# micromouse.net
KiCad netlist of a schematic drawn in EAGLE
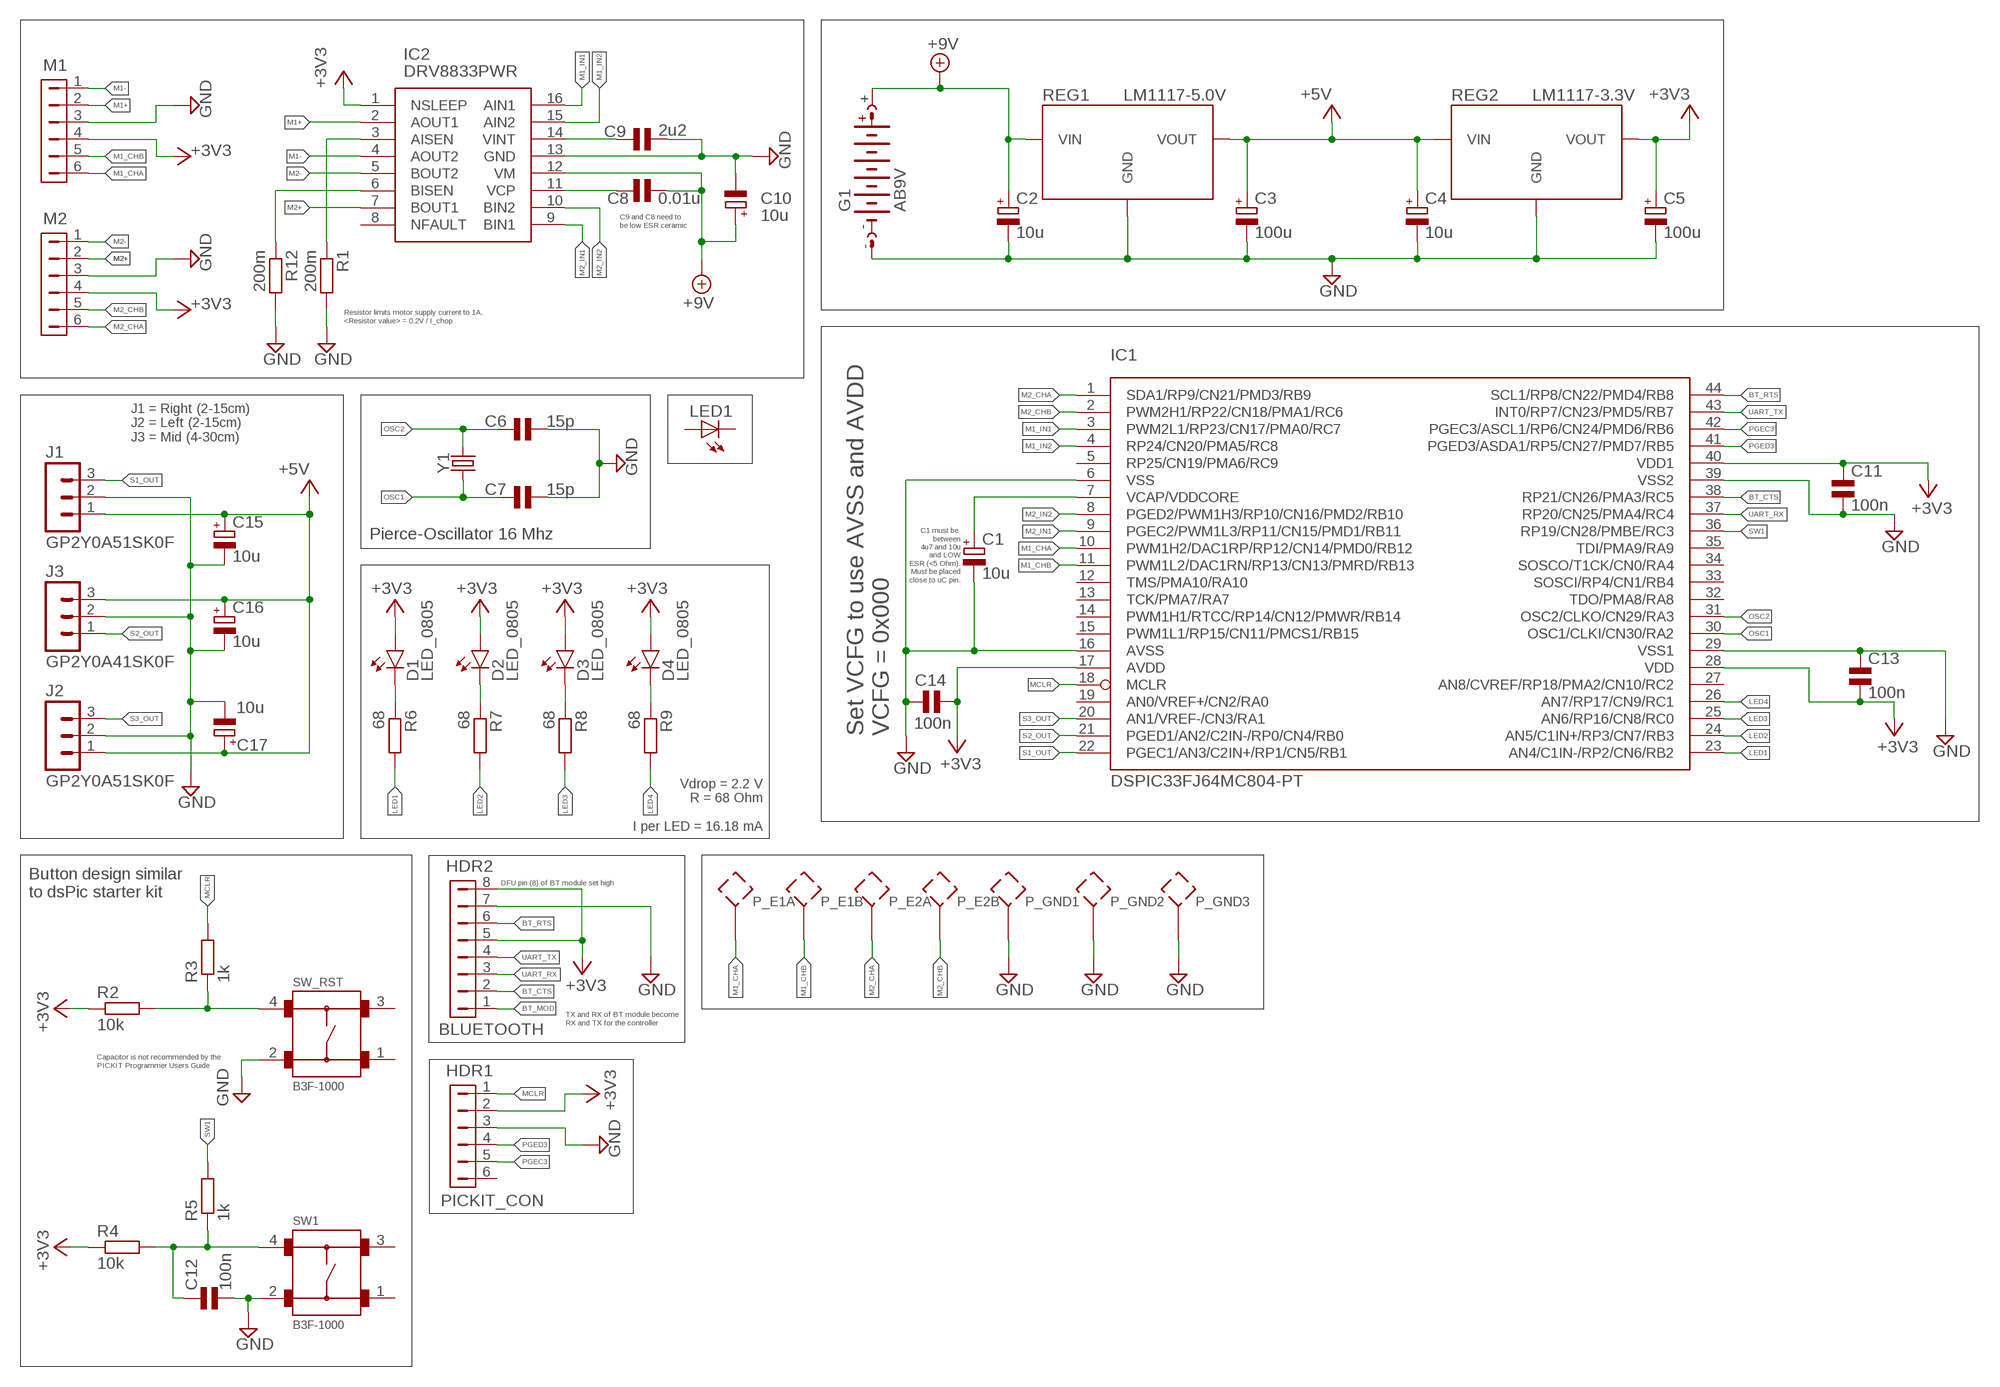
[diagram p0: schematic, sheet 1]

(export (version "E")
  (design (tool "Eeschema 10.0.6"))
  (components
    (comp (ref "C1")
      (value "10u")
      (footprint "eagle-import:0805_POL")
      (libsource (lib "eagle-import") (part "CPOL_0805"))
    )
    (comp (ref "C2")
      (value "10u")
      (footprint "eagle-import:0805_POL")
      (libsource (lib "eagle-import") (part "CPOL_0805"))
    )
    (comp (ref "C3")
      (value "100u")
      (footprint "eagle-import:0805_POL")
      (libsource (lib "eagle-import") (part "CPOL_0805"))
    )
    (comp (ref "C4")
      (value "10u")
      (footprint "eagle-import:0805_POL")
      (libsource (lib "eagle-import") (part "CPOL_0805"))
    )
    (comp (ref "C5")
      (value "100u")
      (footprint "eagle-import:0805_POL")
      (libsource (lib "eagle-import") (part "CPOL_0805"))
    )
    (comp (ref "C6")
      (value "15p")
      (footprint "eagle-import:0805")
      (libsource (lib "eagle-import") (part "C_0805"))
    )
    (comp (ref "C7")
      (value "15p")
      (footprint "eagle-import:0805")
      (libsource (lib "eagle-import") (part "C_0805"))
    )
    (comp (ref "C8")
      (value "0.01u")
      (footprint "eagle-import:0805")
      (libsource (lib "eagle-import") (part "C_0805"))
    )
    (comp (ref "C9")
      (value "2u2")
      (footprint "eagle-import:0805")
      (libsource (lib "eagle-import") (part "C_0805"))
    )
    (comp (ref "C10")
      (value "10u")
      (footprint "eagle-import:0805_POL")
      (libsource (lib "eagle-import") (part "CPOL_0805"))
    )
    (comp (ref "C11")
      (value "100n")
      (footprint "eagle-import:0805")
      (libsource (lib "eagle-import") (part "C_0805"))
    )
    (comp (ref "C12")
      (value "100n")
      (footprint "eagle-import:0805")
      (libsource (lib "eagle-import") (part "C_0805"))
    )
    (comp (ref "C13")
      (value "100n")
      (footprint "eagle-import:0805")
      (libsource (lib "eagle-import") (part "C_0805"))
    )
    (comp (ref "C14")
      (value "100n")
      (footprint "eagle-import:0805")
      (libsource (lib "eagle-import") (part "C_0805"))
    )
    (comp (ref "C15")
      (value "10u")
      (footprint "eagle-import:0805_POL")
      (libsource (lib "eagle-import") (part "CPOL_0805"))
    )
    (comp (ref "C16")
      (value "10u")
      (footprint "eagle-import:0805_POL")
      (libsource (lib "eagle-import") (part "CPOL_0805"))
    )
    (comp (ref "C17")
      (value "10u")
      (footprint "eagle-import:0805_POL")
      (libsource (lib "eagle-import") (part "CPOL_0805"))
    )
    (comp (ref "D1")
      (value "LED_0805")
      (footprint "eagle-import:SMD_LED_0805")
      (libsource (lib "eagle-import") (part "LED_0805"))
    )
    (comp (ref "D2")
      (value "LED_0805")
      (footprint "eagle-import:SMD_LED_0805")
      (libsource (lib "eagle-import") (part "LED_0805"))
    )
    (comp (ref "D3")
      (value "LED_0805")
      (footprint "eagle-import:SMD_LED_0805")
      (libsource (lib "eagle-import") (part "LED_0805"))
    )
    (comp (ref "D4")
      (value "LED_0805")
      (footprint "eagle-import:SMD_LED_0805")
      (libsource (lib "eagle-import") (part "LED_0805"))
    )
    (comp (ref "G1")
      (value "AB9V")
      (footprint "eagle-import:AB9V")
      (libsource (lib "eagle-import") (part "AB9V"))
    )
    (comp (ref "HDR1")
      (value "PICKIT_CON")
      (footprint "eagle-import:6PIN")
      (libsource (lib "eagle-import") (part "PICKIT_CON"))
    )
    (comp (ref "HDR2")
      (value "BLUETOOTH")
      (footprint "eagle-import:1X08")
      (libsource (lib "eagle-import") (part "BLUETOOTHSHIELD"))
    )
    (comp (ref "IC1")
      (value "DSPIC33FJ64MC804-PT")
      (footprint "eagle-import:TQFP44")
      (libsource (lib "eagle-import") (part "DSPIC33FJ64MC804-PT"))
    )
    (comp (ref "IC2")
      (value "DRV8833PWR")
      (footprint "eagle-import:SOP65P640X120-16N")
      (fields (field (name "MOUSER_PART_NUMBER") "595-DRV8833PWR"))
      (libsource (lib "eagle-import") (part "DRV8833PWR"))
    )
    (comp (ref "J1")
      (value "GP2Y0A51SK0F")
      (footprint "eagle-import:B3B-ZR(LF)(SN)")
      (libsource (lib "eagle-import") (part "B3B-ZR"))
    )
    (comp (ref "J2")
      (value "GP2Y0A51SK0F")
      (footprint "eagle-import:B3B-ZR(LF)(SN)")
      (libsource (lib "eagle-import") (part "B3B-ZR"))
    )
    (comp (ref "J3")
      (value "GP2Y0A41SK0F")
      (footprint "eagle-import:B3B-PH-K-S")
      (libsource (lib "eagle-import") (part "B3B-PH-K-S"))
    )
    (comp (ref "LED1")
      (value "LED5MM")
      (footprint "eagle-import:LED5MM")
      (libsource (lib "eagle-import") (part "LED5MM"))
    )
    (comp (ref "M1")
      (value "MOTOR_CON")
      (footprint "eagle-import:JP3Q")
      (libsource (lib "eagle-import") (part "MOTOR_CON"))
    )
    (comp (ref "M2")
      (value "MOTOR_CON")
      (footprint "eagle-import:JP3Q")
      (libsource (lib "eagle-import") (part "MOTOR_CON"))
    )
    (comp (ref "P_E1A")
      (value "PROBE_POINTTHT")
      (footprint "eagle-import:PROBEPOINT_THT")
      (libsource (lib "eagle-import") (part "PROBE_POINTTHT"))
    )
    (comp (ref "P_E1B")
      (value "PROBE_POINTTHT")
      (footprint "eagle-import:PROBEPOINT_THT")
      (libsource (lib "eagle-import") (part "PROBE_POINTTHT"))
    )
    (comp (ref "P_E2A")
      (value "PROBE_POINTTHT")
      (footprint "eagle-import:PROBEPOINT_THT")
      (libsource (lib "eagle-import") (part "PROBE_POINTTHT"))
    )
    (comp (ref "P_E2B")
      (value "PROBE_POINTTHT")
      (footprint "eagle-import:PROBEPOINT_THT")
      (libsource (lib "eagle-import") (part "PROBE_POINTTHT"))
    )
    (comp (ref "P_GND1")
      (value "PROBE_POINTTHT")
      (footprint "eagle-import:PROBEPOINT_THT")
      (libsource (lib "eagle-import") (part "PROBE_POINTTHT"))
    )
    (comp (ref "P_GND2")
      (value "PROBE_POINTTHT")
      (footprint "eagle-import:PROBEPOINT_THT")
      (libsource (lib "eagle-import") (part "PROBE_POINTTHT"))
    )
    (comp (ref "P_GND3")
      (value "PROBE_POINTTHT")
      (footprint "eagle-import:PROBEPOINT_THT")
      (libsource (lib "eagle-import") (part "PROBE_POINTTHT"))
    )
    (comp (ref "R1")
      (value "200m")
      (footprint "eagle-import:0805")
      (libsource (lib "eagle-import") (part "R_0805"))
    )
    (comp (ref "R2")
      (value "10k")
      (footprint "eagle-import:0805")
      (libsource (lib "eagle-import") (part "R_0805"))
    )
    (comp (ref "R3")
      (value "1k")
      (footprint "eagle-import:0805")
      (libsource (lib "eagle-import") (part "R_0805"))
    )
    (comp (ref "R4")
      (value "10k")
      (footprint "eagle-import:0805")
      (libsource (lib "eagle-import") (part "R_0805"))
    )
    (comp (ref "R5")
      (value "1k")
      (footprint "eagle-import:0805")
      (libsource (lib "eagle-import") (part "R_0805"))
    )
    (comp (ref "R6")
      (value "68")
      (footprint "eagle-import:0805")
      (libsource (lib "eagle-import") (part "R_0805"))
    )
    (comp (ref "R7")
      (value "68")
      (footprint "eagle-import:0805")
      (libsource (lib "eagle-import") (part "R_0805"))
    )
    (comp (ref "R8")
      (value "68")
      (footprint "eagle-import:0805")
      (libsource (lib "eagle-import") (part "R_0805"))
    )
    (comp (ref "R9")
      (value "68")
      (footprint "eagle-import:0805")
      (libsource (lib "eagle-import") (part "R_0805"))
    )
    (comp (ref "R12")
      (value "200m")
      (footprint "eagle-import:0805")
      (libsource (lib "eagle-import") (part "R_0805"))
    )
    (comp (ref "REG1")
      (value "LM1117-5.0V")
      (footprint "eagle-import:SOT-223-4")
      (libsource (lib "eagle-import") (part "LM1117_SOT223"))
    )
    (comp (ref "REG2")
      (value "LM1117-3.3V")
      (footprint "eagle-import:SOT-223-4")
      (libsource (lib "eagle-import") (part "LM1117_SOT223"))
    )
    (comp (ref "SW1")
      (value "B3F-1000")
      (footprint "eagle-import:B3F-1000")
      (fields
        (field (name "DIGI_KEY_PART_NUMBER") "SW400-ND")
        (field (name "MANUFACTURER") "Omron Electronics Inc-EMC Div")
        (field (name "CREATED_BY") "PCBLayout.com")
      )
      (libsource (lib "eagle-import") (part "B3F-1000"))
    )
    (comp (ref "SW_RST")
      (value "B3F-1000")
      (footprint "eagle-import:B3F-1000")
      (fields
        (field (name "DIGI_KEY_PART_NUMBER") "SW400-ND")
        (field (name "MANUFACTURER") "Omron Electronics Inc-EMC Div")
        (field (name "CREATED_BY") "PCBLayout.com")
      )
      (libsource (lib "eagle-import") (part "B3F-1000"))
    )
    (comp (ref "Y1")
      (value "CRYSTALPTH-HC49US")
      (footprint "eagle-import:HC49US")
      (libsource (lib "eagle-import") (part "CRYSTALPTH-HC49US"))
    )
  )
  (nets
    (net (code "1") (name "+3V3") (class "Default")
      (node (ref "C11") (pin "1") (pinfunction "+_1") (pintype "passive"))
      (node (ref "C13") (pin "2") (pinfunction "-_2") (pintype "passive"))
      (node (ref "C14") (pin "2") (pinfunction "-_2") (pintype "passive"))
      (node (ref "C5") (pin "1") (pinfunction "+_1") (pintype "passive"))
      (node (ref "D1") (pin "P$2") (pinfunction "A_P$2") (pintype "passive"))
      (node (ref "D2") (pin "P$2") (pinfunction "A_P$2") (pintype "passive"))
      (node (ref "D3") (pin "P$2") (pinfunction "A_P$2") (pintype "passive"))
      (node (ref "D4") (pin "P$2") (pinfunction "A_P$2") (pintype "passive"))
      (node (ref "HDR1") (pin "2") (pinfunction "2_2") (pintype "passive"))
      (node (ref "HDR2") (pin "5") (pinfunction "5_5") (pintype "passive"))
      (node (ref "HDR2") (pin "8") (pinfunction "8_8") (pintype "passive"))
      (node (ref "IC1") (pin "17") (pinfunction "AVDD_17") (pintype "power_in"))
      (node (ref "IC1") (pin "28") (pinfunction "VDD_28") (pintype "power_in"))
      (node (ref "IC1") (pin "40") (pinfunction "VDD1_40") (pintype "power_in"))
      (node (ref "IC2") (pin "1") (pinfunction "NSLEEP_1") (pintype "bidirectional"))
      (node (ref "M1") (pin "4") (pinfunction "4_4") (pintype "passive"))
      (node (ref "M2") (pin "4") (pinfunction "4_4") (pintype "passive"))
      (node (ref "R2") (pin "1") (pinfunction "1_1") (pintype "passive"))
      (node (ref "R4") (pin "1") (pinfunction "1_1") (pintype "passive"))
      (node (ref "REG2") (pin "2") (pinfunction "VOUT_2") (pintype "bidirectional"))
      (node (ref "REG2") (pin "4") (pinfunction "VOUT_4") (pintype "bidirectional"))
    )
    (net (code "2") (name "+5V") (class "Default")
      (node (ref "C15") (pin "1") (pinfunction "+_1") (pintype "passive"))
      (node (ref "C16") (pin "1") (pinfunction "+_1") (pintype "passive"))
      (node (ref "C17") (pin "1") (pinfunction "+_1") (pintype "passive"))
      (node (ref "C3") (pin "1") (pinfunction "+_1") (pintype "passive"))
      (node (ref "C4") (pin "1") (pinfunction "+_1") (pintype "passive"))
      (node (ref "J1") (pin "1") (pinfunction "1_1") (pintype "passive"))
      (node (ref "J2") (pin "1") (pinfunction "1_1") (pintype "passive"))
      (node (ref "J3") (pin "3") (pinfunction "3_3") (pintype "passive"))
      (node (ref "REG1") (pin "2") (pinfunction "VOUT_2") (pintype "bidirectional"))
      (node (ref "REG1") (pin "4") (pinfunction "VOUT_4") (pintype "bidirectional"))
      (node (ref "REG2") (pin "3") (pinfunction "VIN_3") (pintype "bidirectional"))
    )
    (net (code "3") (name "+9V") (class "Default")
      (node (ref "C10") (pin "1") (pinfunction "+_1") (pintype "passive"))
      (node (ref "C2") (pin "1") (pinfunction "+_1") (pintype "passive"))
      (node (ref "C8") (pin "1") (pinfunction "+_1") (pintype "passive"))
      (node (ref "G1") (pin "+") (pinfunction "+_+") (pintype "passive"))
      (node (ref "IC2") (pin "12") (pinfunction "VM_12") (pintype "bidirectional"))
      (node (ref "REG1") (pin "3") (pinfunction "VIN_3") (pintype "bidirectional"))
    )
    (net (code "4") (name "BT_CTS") (class "Default")
      (node (ref "HDR2") (pin "2") (pinfunction "2_2") (pintype "passive"))
      (node (ref "IC1") (pin "38") (pinfunction "RP21/CN26/PMA3/RC5_38") (pintype "bidirectional"))
    )
    (net (code "5") (name "BT_MOD") (class "Default")
      (node (ref "HDR2") (pin "1") (pinfunction "1_1") (pintype "passive"))
    )
    (net (code "6") (name "BT_RTS") (class "Default")
      (node (ref "HDR2") (pin "6") (pinfunction "6_6") (pintype "passive"))
      (node (ref "IC1") (pin "44") (pinfunction "SCL1/RP8/CN22/PMD4/RB8_44") (pintype "bidirectional"))
    )
    (net (code "7") (name "GND") (class "Default")
      (node (ref "C1") (pin "2") (pinfunction "-_2") (pintype "passive"))
      (node (ref "C10") (pin "2") (pinfunction "-_2") (pintype "passive"))
      (node (ref "C11") (pin "2") (pinfunction "-_2") (pintype "passive"))
      (node (ref "C12") (pin "2") (pinfunction "-_2") (pintype "passive"))
      (node (ref "C13") (pin "1") (pinfunction "+_1") (pintype "passive"))
      (node (ref "C14") (pin "1") (pinfunction "+_1") (pintype "passive"))
      (node (ref "C15") (pin "2") (pinfunction "-_2") (pintype "passive"))
      (node (ref "C16") (pin "2") (pinfunction "-_2") (pintype "passive"))
      (node (ref "C17") (pin "2") (pinfunction "-_2") (pintype "passive"))
      (node (ref "C2") (pin "2") (pinfunction "-_2") (pintype "passive"))
      (node (ref "C3") (pin "2") (pinfunction "-_2") (pintype "passive"))
      (node (ref "C4") (pin "2") (pinfunction "-_2") (pintype "passive"))
      (node (ref "C5") (pin "2") (pinfunction "-_2") (pintype "passive"))
      (node (ref "C6") (pin "2") (pinfunction "-_2") (pintype "passive"))
      (node (ref "C7") (pin "2") (pinfunction "-_2") (pintype "passive"))
      (node (ref "C9") (pin "2") (pinfunction "-_2") (pintype "passive"))
      (node (ref "G1") (pin "-") (pinfunction "-_-") (pintype "passive"))
      (node (ref "HDR1") (pin "3") (pinfunction "3_3") (pintype "passive"))
      (node (ref "HDR2") (pin "7") (pinfunction "7_7") (pintype "passive"))
      (node (ref "IC1") (pin "16") (pinfunction "AVSS_16") (pintype "power_in"))
      (node (ref "IC1") (pin "29") (pinfunction "VSS1_29") (pintype "power_in"))
      (node (ref "IC1") (pin "39") (pinfunction "VSS2_39") (pintype "power_in"))
      (node (ref "IC1") (pin "6") (pinfunction "VSS_6") (pintype "power_in"))
      (node (ref "IC2") (pin "13") (pinfunction "GND_13") (pintype "bidirectional"))
      (node (ref "J1") (pin "2") (pinfunction "2_2") (pintype "passive"))
      (node (ref "J2") (pin "2") (pinfunction "2_2") (pintype "passive"))
      (node (ref "J3") (pin "2") (pinfunction "2_2") (pintype "passive"))
      (node (ref "M1") (pin "3") (pinfunction "3_3") (pintype "passive"))
      (node (ref "M2") (pin "3") (pinfunction "3_3") (pintype "passive"))
      (node (ref "P_GND1") (pin "P$1") (pinfunction "P$1_P$1") (pintype "bidirectional"))
      (node (ref "P_GND2") (pin "P$1") (pinfunction "P$1_P$1") (pintype "bidirectional"))
      (node (ref "P_GND3") (pin "P$1") (pinfunction "P$1_P$1") (pintype "bidirectional"))
      (node (ref "R1") (pin "2") (pinfunction "2_2") (pintype "passive"))
      (node (ref "R12") (pin "2") (pinfunction "2_2") (pintype "passive"))
      (node (ref "REG1") (pin "1") (pinfunction "GND_1") (pintype "bidirectional"))
      (node (ref "REG2") (pin "1") (pinfunction "GND_1") (pintype "bidirectional"))
      (node (ref "SW1") (pin "2") (pinfunction "2_2") (pintype "passive"))
      (node (ref "SW_RST") (pin "2") (pinfunction "2_2") (pintype "passive"))
    )
    (net (code "8") (name "LED1") (class "Default")
      (node (ref "IC1") (pin "23") (pinfunction "AN4/C1IN-/RP2/CN6/RB2_23") (pintype "bidirectional"))
      (node (ref "R6") (pin "2") (pinfunction "2_2") (pintype "passive"))
    )
    (net (code "9") (name "LED2") (class "Default")
      (node (ref "IC1") (pin "24") (pinfunction "AN5/C1IN+/RP3/CN7/RB3_24") (pintype "bidirectional"))
      (node (ref "R7") (pin "2") (pinfunction "2_2") (pintype "passive"))
    )
    (net (code "10") (name "LED3") (class "Default")
      (node (ref "IC1") (pin "25") (pinfunction "AN6/RP16/CN8/RC0_25") (pintype "bidirectional"))
      (node (ref "R8") (pin "2") (pinfunction "2_2") (pintype "passive"))
    )
    (net (code "11") (name "LED4") (class "Default")
      (node (ref "IC1") (pin "26") (pinfunction "AN7/RP17/CN9/RC1_26") (pintype "bidirectional"))
      (node (ref "R9") (pin "2") (pinfunction "2_2") (pintype "passive"))
    )
    (net (code "12") (name "M1+") (class "Default")
      (node (ref "IC2") (pin "2") (pinfunction "AOUT1_2") (pintype "bidirectional"))
      (node (ref "M1") (pin "2") (pinfunction "2_2") (pintype "passive"))
    )
    (net (code "13") (name "M1-") (class "Default")
      (node (ref "IC2") (pin "4") (pinfunction "AOUT2_4") (pintype "bidirectional"))
      (node (ref "M1") (pin "1") (pinfunction "1_1") (pintype "passive"))
    )
    (net (code "14") (name "M1_CHA") (class "Default")
      (node (ref "IC1") (pin "10") (pinfunction "PWM1H2/DAC1RP/RP12/CN14/PMD0/RB12_10") (pintype "bidirectional"))
      (node (ref "M1") (pin "6") (pinfunction "6_6") (pintype "passive"))
      (node (ref "P_E1A") (pin "P$1") (pinfunction "P$1_P$1") (pintype "bidirectional"))
    )
    (net (code "15") (name "M1_CHB") (class "Default")
      (node (ref "IC1") (pin "11") (pinfunction "PWM1L2/DAC1RN/RP13/CN13/PMRD/RB13_11") (pintype "bidirectional"))
      (node (ref "M1") (pin "5") (pinfunction "5_5") (pintype "passive"))
      (node (ref "P_E1B") (pin "P$1") (pinfunction "P$1_P$1") (pintype "bidirectional"))
    )
    (net (code "16") (name "M1_IN1") (class "Default")
      (node (ref "IC1") (pin "3") (pinfunction "PWM2L1/RP23/CN17/PMA0/RC7_3") (pintype "bidirectional"))
      (node (ref "IC2") (pin "16") (pinfunction "AIN1_16") (pintype "bidirectional"))
    )
    (net (code "17") (name "M1_IN2") (class "Default")
      (node (ref "IC1") (pin "4") (pinfunction "RP24/CN20/PMA5/RC8_4") (pintype "bidirectional"))
      (node (ref "IC2") (pin "15") (pinfunction "AIN2_15") (pintype "bidirectional"))
    )
    (net (code "18") (name "M2+") (class "Default")
      (node (ref "IC2") (pin "7") (pinfunction "BOUT1_7") (pintype "bidirectional"))
      (node (ref "M2") (pin "2") (pinfunction "2_2") (pintype "passive"))
    )
    (net (code "19") (name "M2-") (class "Default")
      (node (ref "IC2") (pin "5") (pinfunction "BOUT2_5") (pintype "bidirectional"))
      (node (ref "M2") (pin "1") (pinfunction "1_1") (pintype "passive"))
    )
    (net (code "20") (name "M2_CHA") (class "Default")
      (node (ref "IC1") (pin "1") (pinfunction "SDA1/RP9/CN21/PMD3/RB9_1") (pintype "bidirectional"))
      (node (ref "M2") (pin "6") (pinfunction "6_6") (pintype "passive"))
      (node (ref "P_E2A") (pin "P$1") (pinfunction "P$1_P$1") (pintype "bidirectional"))
    )
    (net (code "21") (name "M2_CHB") (class "Default")
      (node (ref "IC1") (pin "2") (pinfunction "PWM2H1/RP22/CN18/PMA1/RC6_2") (pintype "bidirectional"))
      (node (ref "M2") (pin "5") (pinfunction "5_5") (pintype "passive"))
      (node (ref "P_E2B") (pin "P$1") (pinfunction "P$1_P$1") (pintype "bidirectional"))
    )
    (net (code "22") (name "M2_IN1") (class "Default")
      (node (ref "IC1") (pin "9") (pinfunction "PGEC2/PWM1L3/RP11/CN15/PMD1/RB11_9") (pintype "bidirectional"))
      (node (ref "IC2") (pin "9") (pinfunction "BIN1_9") (pintype "bidirectional"))
    )
    (net (code "23") (name "M2_IN2") (class "Default")
      (node (ref "IC1") (pin "8") (pinfunction "PGED2/PWM1H3/RP10/CN16/PMD2/RB10_8") (pintype "bidirectional"))
      (node (ref "IC2") (pin "10") (pinfunction "BIN2_10") (pintype "bidirectional"))
    )
    (net (code "24") (name "MCLR") (class "Default")
      (node (ref "HDR1") (pin "1") (pinfunction "1_1") (pintype "passive"))
      (node (ref "IC1") (pin "18") (pinfunction "MCLR_18") (pintype "input"))
      (node (ref "R3") (pin "2") (pinfunction "2_2") (pintype "passive"))
    )
    (net (code "25") (name "Net-(C1-+)") (class "Default")
      (node (ref "C1") (pin "1") (pinfunction "+_1") (pintype "passive"))
      (node (ref "IC1") (pin "7") (pinfunction "VCAP/VDDCORE_7") (pintype "power_in"))
    )
    (net (code "26") (name "Net-(C8--)") (class "Default")
      (node (ref "C8") (pin "2") (pinfunction "-_2") (pintype "passive"))
      (node (ref "IC2") (pin "11") (pinfunction "VCP_11") (pintype "bidirectional"))
    )
    (net (code "27") (name "Net-(C9-+)") (class "Default")
      (node (ref "C9") (pin "1") (pinfunction "+_1") (pintype "passive"))
      (node (ref "IC2") (pin "14") (pinfunction "VINT_14") (pintype "bidirectional"))
    )
    (net (code "28") (name "Net-(C12-+)") (class "Default")
      (node (ref "C12") (pin "1") (pinfunction "+_1") (pintype "passive"))
      (node (ref "R4") (pin "2") (pinfunction "2_2") (pintype "passive"))
      (node (ref "R5") (pin "1") (pinfunction "1_1") (pintype "passive"))
      (node (ref "SW1") (pin "4") (pinfunction "4_4") (pintype "passive"))
    )
    (net (code "29") (name "Net-(D1-C)") (class "Default")
      (node (ref "D1") (pin "P$1") (pinfunction "C_P$1") (pintype "passive"))
      (node (ref "R6") (pin "1") (pinfunction "1_1") (pintype "passive"))
    )
    (net (code "30") (name "Net-(D2-C)") (class "Default")
      (node (ref "D2") (pin "P$1") (pinfunction "C_P$1") (pintype "passive"))
      (node (ref "R7") (pin "1") (pinfunction "1_1") (pintype "passive"))
    )
    (net (code "31") (name "Net-(D3-C)") (class "Default")
      (node (ref "D3") (pin "P$1") (pinfunction "C_P$1") (pintype "passive"))
      (node (ref "R8") (pin "1") (pinfunction "1_1") (pintype "passive"))
    )
    (net (code "32") (name "Net-(D4-C)") (class "Default")
      (node (ref "D4") (pin "P$1") (pinfunction "C_P$1") (pintype "passive"))
      (node (ref "R9") (pin "1") (pinfunction "1_1") (pintype "passive"))
    )
    (net (code "33") (name "Net-(IC2-AISEN)") (class "Default")
      (node (ref "IC2") (pin "3") (pinfunction "AISEN_3") (pintype "bidirectional"))
      (node (ref "R1") (pin "1") (pinfunction "1_1") (pintype "passive"))
    )
    (net (code "34") (name "Net-(IC2-BISEN)") (class "Default")
      (node (ref "IC2") (pin "6") (pinfunction "BISEN_6") (pintype "bidirectional"))
      (node (ref "R12") (pin "1") (pinfunction "1_1") (pintype "passive"))
    )
    (net (code "35") (name "Net-(R2-Pad2)") (class "Default")
      (node (ref "R2") (pin "2") (pinfunction "2_2") (pintype "passive"))
      (node (ref "R3") (pin "1") (pinfunction "1_1") (pintype "passive"))
      (node (ref "SW_RST") (pin "4") (pinfunction "4_4") (pintype "passive"))
    )
    (net (code "36") (name "OSC1") (class "Default")
      (node (ref "C7") (pin "1") (pinfunction "+_1") (pintype "passive"))
      (node (ref "IC1") (pin "30") (pinfunction "OSC1/CLKI/CN30/RA2_30") (pintype "bidirectional"))
      (node (ref "Y1") (pin "1") (pinfunction "1_1") (pintype "passive"))
    )
    (net (code "37") (name "OSC2") (class "Default")
      (node (ref "C6") (pin "1") (pinfunction "+_1") (pintype "passive"))
      (node (ref "IC1") (pin "31") (pinfunction "OSC2/CLKO/CN29/RA3_31") (pintype "bidirectional"))
      (node (ref "Y1") (pin "2") (pinfunction "2_2") (pintype "passive"))
    )
    (net (code "38") (name "PGEC3") (class "Default")
      (node (ref "HDR1") (pin "5") (pinfunction "5_5") (pintype "passive"))
      (node (ref "IC1") (pin "42") (pinfunction "PGEC3/ASCL1/RP6/CN24/PMD6/RB6_42") (pintype "bidirectional"))
    )
    (net (code "39") (name "PGED3") (class "Default")
      (node (ref "HDR1") (pin "4") (pinfunction "4_4") (pintype "passive"))
      (node (ref "IC1") (pin "41") (pinfunction "PGED3/ASDA1/RP5/CN27/PMD7/RB5_41") (pintype "bidirectional"))
    )
    (net (code "40") (name "S1_OUT") (class "Default")
      (node (ref "IC1") (pin "22") (pinfunction "PGEC1/AN3/C2IN+/RP1/CN5/RB1_22") (pintype "bidirectional"))
      (node (ref "J1") (pin "3") (pinfunction "3_3") (pintype "passive"))
    )
    (net (code "41") (name "S2_OUT") (class "Default")
      (node (ref "IC1") (pin "21") (pinfunction "PGED1/AN2/C2IN-/RP0/CN4/RB0_21") (pintype "bidirectional"))
      (node (ref "J3") (pin "1") (pinfunction "1_1") (pintype "passive"))
    )
    (net (code "42") (name "S3_OUT") (class "Default")
      (node (ref "IC1") (pin "20") (pinfunction "AN1/VREF-/CN3/RA1_20") (pintype "bidirectional"))
      (node (ref "J2") (pin "3") (pinfunction "3_3") (pintype "passive"))
    )
    (net (code "43") (name "SW1") (class "Default")
      (node (ref "IC1") (pin "36") (pinfunction "RP19/CN28/PMBE/RC3_36") (pintype "bidirectional"))
      (node (ref "R5") (pin "2") (pinfunction "2_2") (pintype "passive"))
    )
    (net (code "44") (name "UART_RX") (class "Default")
      (node (ref "HDR2") (pin "3") (pinfunction "3_3") (pintype "passive"))
      (node (ref "IC1") (pin "37") (pinfunction "RP20/CN25/PMA4/RC4_37") (pintype "bidirectional"))
    )
    (net (code "45") (name "UART_TX") (class "Default")
      (node (ref "HDR2") (pin "4") (pinfunction "4_4") (pintype "passive"))
      (node (ref "IC1") (pin "43") (pinfunction "INT0/RP7/CN23/PMD5/RB7_43") (pintype "bidirectional"))
    )
    (net (code "46") (name "unconnected-(HDR1-Pad6)") (class "Default")
      (node (ref "HDR1") (pin "6") (pinfunction "6_6") (pintype "passive"))
    )
    (net (code "47") (name "unconnected-(IC1-AN0{slash}VREF+{slash}CN2{slash}RA0-Pad19)") (class "Default")
      (node (ref "IC1") (pin "19") (pinfunction "AN0/VREF+/CN2/RA0_19") (pintype "bidirectional"))
    )
    (net (code "48") (name "unconnected-(IC1-AN8{slash}CVREF{slash}RP18{slash}PMA2{slash}CN10{slash}RC2-Pad27)") (class "Default")
      (node (ref "IC1") (pin "27") (pinfunction "AN8/CVREF/RP18/PMA2/CN10/RC2_27") (pintype "bidirectional"))
    )
    (net (code "49") (name "unconnected-(IC1-PWM1H1{slash}RTCC{slash}RP14{slash}CN12{slash}PMWR{slash}RB14-Pad14)") (class "Default")
      (node (ref "IC1") (pin "14") (pinfunction "PWM1H1/RTCC/RP14/CN12/PMWR/RB14_14") (pintype "bidirectional"))
    )
    (net (code "50") (name "unconnected-(IC1-PWM1L1{slash}RP15{slash}CN11{slash}PMCS1{slash}RB15-Pad15)") (class "Default")
      (node (ref "IC1") (pin "15") (pinfunction "PWM1L1/RP15/CN11/PMCS1/RB15_15") (pintype "bidirectional"))
    )
    (net (code "51") (name "unconnected-(IC1-RP25{slash}CN19{slash}PMA6{slash}RC9-Pad5)") (class "Default")
      (node (ref "IC1") (pin "5") (pinfunction "RP25/CN19/PMA6/RC9_5") (pintype "bidirectional"))
    )
    (net (code "52") (name "unconnected-(IC1-SOSCI{slash}RP4{slash}CN1{slash}RB4-Pad33)") (class "Default")
      (node (ref "IC1") (pin "33") (pinfunction "SOSCI/RP4/CN1/RB4_33") (pintype "bidirectional"))
    )
    (net (code "53") (name "unconnected-(IC1-SOSCO{slash}T1CK{slash}CN0{slash}RA4-Pad34)") (class "Default")
      (node (ref "IC1") (pin "34") (pinfunction "SOSCO/T1CK/CN0/RA4_34") (pintype "bidirectional"))
    )
    (net (code "54") (name "unconnected-(IC1-TCK{slash}PMA7{slash}RA7-Pad13)") (class "Default")
      (node (ref "IC1") (pin "13") (pinfunction "TCK/PMA7/RA7_13") (pintype "bidirectional"))
    )
    (net (code "55") (name "unconnected-(IC1-TDI{slash}PMA9{slash}RA9-Pad35)") (class "Default")
      (node (ref "IC1") (pin "35") (pinfunction "TDI/PMA9/RA9_35") (pintype "bidirectional"))
    )
    (net (code "56") (name "unconnected-(IC1-TDO{slash}PMA8{slash}RA8-Pad32)") (class "Default")
      (node (ref "IC1") (pin "32") (pinfunction "TDO/PMA8/RA8_32") (pintype "bidirectional"))
    )
    (net (code "57") (name "unconnected-(IC1-TMS{slash}PMA10{slash}RA10-Pad12)") (class "Default")
      (node (ref "IC1") (pin "12") (pinfunction "TMS/PMA10/RA10_12") (pintype "bidirectional"))
    )
    (net (code "58") (name "unconnected-(IC2-NFAULT-Pad8)") (class "Default")
      (node (ref "IC2") (pin "8") (pinfunction "NFAULT_8") (pintype "bidirectional"))
    )
    (net (code "59") (name "unconnected-(LED1-C-PadK)") (class "Default")
      (node (ref "LED1") (pin "K") (pinfunction "C_K") (pintype "passive"))
    )
    (net (code "60") (name "unconnected-(LED1-PadA)") (class "Default")
      (node (ref "LED1") (pin "A") (pinfunction "A_A") (pintype "passive"))
    )
    (net (code "61") (name "unconnected-(SW1-Pad1)") (class "Default")
      (node (ref "SW1") (pin "1") (pinfunction "1_1") (pintype "passive"))
    )
    (net (code "62") (name "unconnected-(SW1-Pad3)") (class "Default")
      (node (ref "SW1") (pin "3") (pinfunction "3_3") (pintype "passive"))
    )
    (net (code "63") (name "unconnected-(SW_RST-Pad1)") (class "Default")
      (node (ref "SW_RST") (pin "1") (pinfunction "1_1") (pintype "passive"))
    )
    (net (code "64") (name "unconnected-(SW_RST-Pad3)") (class "Default")
      (node (ref "SW_RST") (pin "3") (pinfunction "3_3") (pintype "passive"))
    )
  )
)
